# knitRider_T_1_4_redukce_led.net
KiCad netlist of a schematic drawn in EAGLE
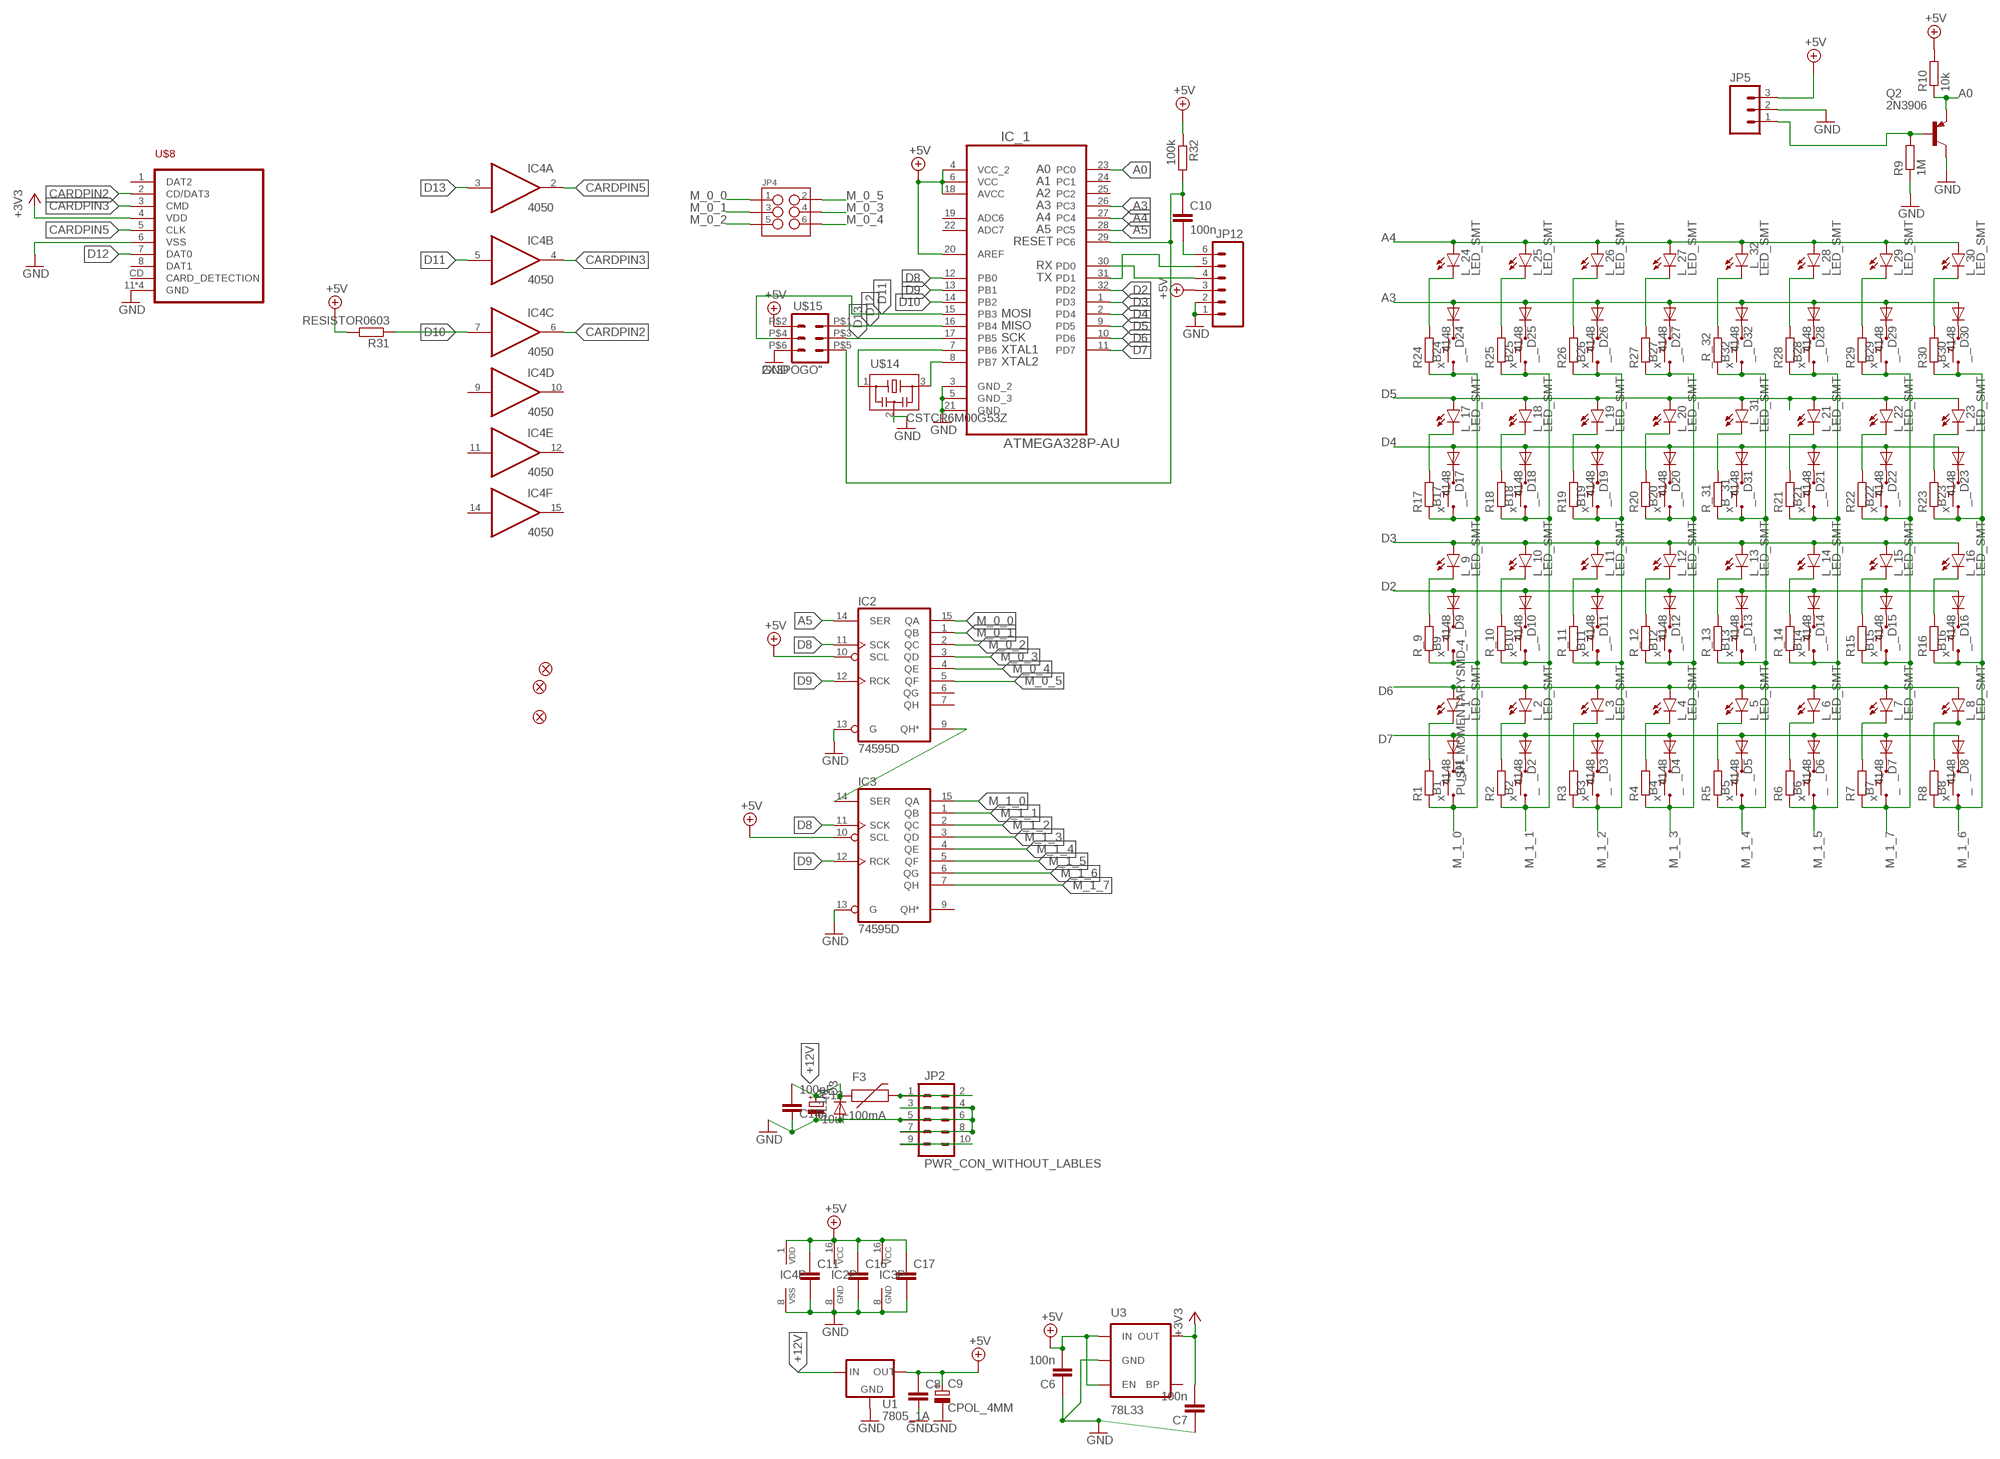
[diagram p0: schematic, sheet 1]

(export (version "E")
  (design (tool "Eeschema 10.0.6"))
  (components
    (comp (ref "B1")
      (value "PUSH_MOMENTARYSMD-4")
      (footprint "eagle-import:TACTILE_SWITCH_TALL")
      (libsource (lib "eagle-import") (part "PUSH_MOMENTARYSMD-4"))
    )
    (comp (ref "B2")
      (value "_")
      (footprint "eagle-import:TACTILE_SWITCH_TALL")
      (libsource (lib "eagle-import") (part "PUSH_MOMENTARYSMD-4"))
    )
    (comp (ref "B3")
      (value "_")
      (footprint "eagle-import:TACTILE_SWITCH_TALL")
      (libsource (lib "eagle-import") (part "PUSH_MOMENTARYSMD-4"))
    )
    (comp (ref "B4")
      (value "_")
      (footprint "eagle-import:TACTILE_SWITCH_TALL")
      (libsource (lib "eagle-import") (part "PUSH_MOMENTARYSMD-4"))
    )
    (comp (ref "B5")
      (value "_")
      (footprint "eagle-import:TACTILE_SWITCH_TALL")
      (libsource (lib "eagle-import") (part "PUSH_MOMENTARYSMD-4"))
    )
    (comp (ref "B6")
      (value "_")
      (footprint "eagle-import:TACTILE_SWITCH_TALL")
      (libsource (lib "eagle-import") (part "PUSH_MOMENTARYSMD-4"))
    )
    (comp (ref "B7")
      (value "_")
      (footprint "eagle-import:TACTILE_SWITCH_TALL")
      (libsource (lib "eagle-import") (part "PUSH_MOMENTARYSMD-4"))
    )
    (comp (ref "B8")
      (value "_")
      (footprint "eagle-import:TACTILE_SWITCH_TALL")
      (libsource (lib "eagle-import") (part "PUSH_MOMENTARYSMD-4"))
    )
    (comp (ref "B9")
      (value "_")
      (footprint "eagle-import:TACTILE_SWITCH_TALL")
      (libsource (lib "eagle-import") (part "PUSH_MOMENTARYSMD-4"))
    )
    (comp (ref "B10")
      (value "_")
      (footprint "eagle-import:TACTILE_SWITCH_TALL")
      (libsource (lib "eagle-import") (part "PUSH_MOMENTARYSMD-4"))
    )
    (comp (ref "B11")
      (value "_")
      (footprint "eagle-import:TACTILE_SWITCH_TALL")
      (libsource (lib "eagle-import") (part "PUSH_MOMENTARYSMD-4"))
    )
    (comp (ref "B12")
      (value "_")
      (footprint "eagle-import:TACTILE_SWITCH_TALL")
      (libsource (lib "eagle-import") (part "PUSH_MOMENTARYSMD-4"))
    )
    (comp (ref "B13")
      (value "_")
      (footprint "eagle-import:TACTILE_SWITCH_TALL")
      (libsource (lib "eagle-import") (part "PUSH_MOMENTARYSMD-4"))
    )
    (comp (ref "B14")
      (value "_")
      (footprint "eagle-import:TACTILE_SWITCH_TALL")
      (libsource (lib "eagle-import") (part "PUSH_MOMENTARYSMD-4"))
    )
    (comp (ref "B15")
      (value "_")
      (footprint "eagle-import:TACTILE_SWITCH_TALL")
      (libsource (lib "eagle-import") (part "PUSH_MOMENTARYSMD-4"))
    )
    (comp (ref "B16")
      (value "_")
      (footprint "eagle-import:TACTILE_SWITCH_TALL")
      (libsource (lib "eagle-import") (part "PUSH_MOMENTARYSMD-4"))
    )
    (comp (ref "B17")
      (value "_")
      (footprint "eagle-import:TACTILE_SWITCH_TALL")
      (libsource (lib "eagle-import") (part "PUSH_MOMENTARYSMD-4"))
    )
    (comp (ref "B18")
      (value "_")
      (footprint "eagle-import:TACTILE_SWITCH_TALL")
      (libsource (lib "eagle-import") (part "PUSH_MOMENTARYSMD-4"))
    )
    (comp (ref "B19")
      (value "_")
      (footprint "eagle-import:TACTILE_SWITCH_TALL")
      (libsource (lib "eagle-import") (part "PUSH_MOMENTARYSMD-4"))
    )
    (comp (ref "B20")
      (value "_")
      (footprint "eagle-import:TACTILE_SWITCH_TALL")
      (libsource (lib "eagle-import") (part "PUSH_MOMENTARYSMD-4"))
    )
    (comp (ref "B21")
      (value "_")
      (footprint "eagle-import:TACTILE_SWITCH_TALL")
      (libsource (lib "eagle-import") (part "PUSH_MOMENTARYSMD-4"))
    )
    (comp (ref "B22")
      (value "_")
      (footprint "eagle-import:TACTILE_SWITCH_TALL")
      (libsource (lib "eagle-import") (part "PUSH_MOMENTARYSMD-4"))
    )
    (comp (ref "B23")
      (value "_")
      (footprint "eagle-import:TACTILE_SWITCH_TALL")
      (libsource (lib "eagle-import") (part "PUSH_MOMENTARYSMD-4"))
    )
    (comp (ref "B24")
      (value "_")
      (footprint "eagle-import:TACTILE_SWITCH_TALL")
      (libsource (lib "eagle-import") (part "PUSH_MOMENTARYSMD-4"))
    )
    (comp (ref "B25")
      (value "_")
      (footprint "eagle-import:TACTILE_SWITCH_TALL")
      (libsource (lib "eagle-import") (part "PUSH_MOMENTARYSMD-4"))
    )
    (comp (ref "B26")
      (value "_")
      (footprint "eagle-import:TACTILE_SWITCH_TALL")
      (libsource (lib "eagle-import") (part "PUSH_MOMENTARYSMD-4"))
    )
    (comp (ref "B27")
      (value "_")
      (footprint "eagle-import:TACTILE_SWITCH_TALL")
      (libsource (lib "eagle-import") (part "PUSH_MOMENTARYSMD-4"))
    )
    (comp (ref "B28")
      (value "_")
      (footprint "eagle-import:TACTILE_SWITCH_TALL")
      (libsource (lib "eagle-import") (part "PUSH_MOMENTARYSMD-4"))
    )
    (comp (ref "B29")
      (value "_")
      (footprint "eagle-import:TACTILE_SWITCH_TALL")
      (libsource (lib "eagle-import") (part "PUSH_MOMENTARYSMD-4"))
    )
    (comp (ref "B30")
      (value "_")
      (footprint "eagle-import:TACTILE_SWITCH_TALL")
      (libsource (lib "eagle-import") (part "PUSH_MOMENTARYSMD-4"))
    )
    (comp (ref "B32")
      (value "_")
      (footprint "eagle-import:TACTILE_SWITCH_TALL")
      (libsource (lib "eagle-import") (part "PUSH_MOMENTARYSMD-4"))
    )
    (comp (ref "B_31")
      (value "_")
      (footprint "eagle-import:TACTILE_SWITCH_TALL")
      (libsource (lib "eagle-import") (part "PUSH_MOMENTARYSMD-4"))
    )
    (comp (ref "C6")
      (value "100n")
      (footprint "eagle-import:CAPACITOR0603")
      (libsource (lib "eagle-import") (part "CAPACITOR0603"))
    )
    (comp (ref "C7")
      (value "100n")
      (footprint "eagle-import:CAPACITOR0603")
      (libsource (lib "eagle-import") (part "CAPACITOR0603"))
    )
    (comp (ref "C8")
      (value "CAPACITOR0603")
      (footprint "eagle-import:CAPACITOR0603")
      (libsource (lib "eagle-import") (part "CAPACITOR0603"))
    )
    (comp (ref "C9")
      (value "CPOL_4MM")
      (footprint "eagle-import:CPOL_4MM")
      (libsource (lib "eagle-import") (part "CPOL_4MM"))
    )
    (comp (ref "C10")
      (value "100n")
      (footprint "eagle-import:CAPACITOR0603")
      (libsource (lib "eagle-import") (part "CAPACITOR0603"))
    )
    (comp (ref "C11")
      (value "CAPACITOR0603")
      (footprint "eagle-import:CAPACITOR0603")
      (libsource (lib "eagle-import") (part "CAPACITOR0603"))
    )
    (comp (ref "C12")
      (value "10uF")
      (footprint "eagle-import:CPOL_4MM")
      (libsource (lib "eagle-import") (part "CPOL_4MM"))
    )
    (comp (ref "C14")
      (value "100nF")
      (footprint "eagle-import:CAPACITOR0603")
      (libsource (lib "eagle-import") (part "CAPACITOR0603"))
    )
    (comp (ref "C16")
      (value "CAPACITOR0603")
      (footprint "eagle-import:CAPACITOR0603")
      (libsource (lib "eagle-import") (part "CAPACITOR0603"))
    )
    (comp (ref "C17")
      (value "CAPACITOR0603")
      (footprint "eagle-import:CAPACITOR0603")
      (libsource (lib "eagle-import") (part "CAPACITOR0603"))
    )
    (comp (ref "D3")
      (value "SL1M")
      (footprint "eagle-import:SOD123")
      (libsource (lib "eagle-import") (part "SL1M"))
    )
    (comp (ref "F3")
      (value "100mA")
      (footprint "eagle-import:PTC0805")
      (libsource (lib "eagle-import") (part "PTC_0805"))
    )
    (comp (ref "FID1")
      (value "FIDUCIAL")
      (footprint "eagle-import:FIDUCIAL")
      (libsource (lib "eagle-import") (part "FIDUCIAL"))
    )
    (comp (ref "FID2")
      (value "FIDUCIAL")
      (footprint "eagle-import:FIDUCIAL")
      (libsource (lib "eagle-import") (part "FIDUCIAL"))
    )
    (comp (ref "FID3")
      (value "FIDUCIAL")
      (footprint "eagle-import:FIDUCIAL")
      (libsource (lib "eagle-import") (part "FIDUCIAL"))
    )
    (comp (ref "IC2")
      (value "74595D")
      (footprint "eagle-import:SO16")
      (fields (field (name "MPN") "SN74HC595DR"))
      (libsource (lib "eagle-import") (part "74595D"))
    )
    (comp (ref "IC3")
      (value "74595D")
      (footprint "eagle-import:SO16")
      (fields (field (name "MPN") "SN74HC595DR"))
      (libsource (lib "eagle-import") (part "74595D"))
    )
    (comp (ref "IC4")
      (value "4050")
      (footprint "eagle-import:SO16")
      (fields (field (name "MPN") "CD4050BDR"))
      (libsource (lib "eagle-import") (part "4050"))
    )
    (comp (ref "IC_1")
      (value "ATMEGA328P-AU")
      (footprint "eagle-import:TQFP32")
      (libsource (lib "eagle-import") (part "ATMEGA328P-AU"))
    )
    (comp (ref "JP2")
      (value "PWR_CON_WITHOUT_LABLES")
      (footprint "eagle-import:PWR_CON_WITHOUT_LABLES")
      (libsource (lib "eagle-import") (part "PWR_CON_WITHOUT_LABLES"))
    )
    (comp (ref "JP4")
      (value "M03X2NO_SILK")
      (footprint "eagle-import:2X3-NS")
      (libsource (lib "eagle-import") (part "M03X2NO_SILK"))
    )
    (comp (ref "JP5")
      (value "M03LOCK")
      (footprint "eagle-import:1X03_LOCK")
      (libsource (lib "eagle-import") (part "M03LOCK"))
    )
    (comp (ref "JP12")
      (value "M06LOCK")
      (footprint "eagle-import:1X06_LOCK")
      (libsource (lib "eagle-import") (part "M06LOCK"))
    )
    (comp (ref "L_1")
      (value "LED_SMT")
      (footprint "eagle-import:LED_0603")
      (libsource (lib "eagle-import") (part "LED_SMT"))
    )
    (comp (ref "L_2")
      (value "LED_SMT")
      (footprint "eagle-import:LED_0603")
      (libsource (lib "eagle-import") (part "LED_SMT"))
    )
    (comp (ref "L_3")
      (value "LED_SMT")
      (footprint "eagle-import:LED_0603")
      (libsource (lib "eagle-import") (part "LED_SMT"))
    )
    (comp (ref "L_4")
      (value "LED_SMT")
      (footprint "eagle-import:LED_0603")
      (libsource (lib "eagle-import") (part "LED_SMT"))
    )
    (comp (ref "L_5")
      (value "LED_SMT")
      (footprint "eagle-import:LED_0603")
      (libsource (lib "eagle-import") (part "LED_SMT"))
    )
    (comp (ref "L_6")
      (value "LED_SMT")
      (footprint "eagle-import:LED_0603")
      (libsource (lib "eagle-import") (part "LED_SMT"))
    )
    (comp (ref "L_7")
      (value "LED_SMT")
      (footprint "eagle-import:LED_0603")
      (libsource (lib "eagle-import") (part "LED_SMT"))
    )
    (comp (ref "L_8")
      (value "LED_SMT")
      (footprint "eagle-import:LED_0603")
      (libsource (lib "eagle-import") (part "LED_SMT"))
    )
    (comp (ref "L_9")
      (value "LED_SMT")
      (footprint "eagle-import:LED_0603")
      (libsource (lib "eagle-import") (part "LED_SMT"))
    )
    (comp (ref "L_10")
      (value "LED_SMT")
      (footprint "eagle-import:LED_0603")
      (libsource (lib "eagle-import") (part "LED_SMT"))
    )
    (comp (ref "L_11")
      (value "LED_SMT")
      (footprint "eagle-import:LED_0603")
      (libsource (lib "eagle-import") (part "LED_SMT"))
    )
    (comp (ref "L_12")
      (value "LED_SMT")
      (footprint "eagle-import:LED_0603")
      (libsource (lib "eagle-import") (part "LED_SMT"))
    )
    (comp (ref "L_13")
      (value "LED_SMT")
      (footprint "eagle-import:LED_0603")
      (libsource (lib "eagle-import") (part "LED_SMT"))
    )
    (comp (ref "L_14")
      (value "LED_SMT")
      (footprint "eagle-import:LED_0603")
      (libsource (lib "eagle-import") (part "LED_SMT"))
    )
    (comp (ref "L_15")
      (value "LED_SMT")
      (footprint "eagle-import:LED_0603")
      (libsource (lib "eagle-import") (part "LED_SMT"))
    )
    (comp (ref "L_16")
      (value "LED_SMT")
      (footprint "eagle-import:LED_0603")
      (libsource (lib "eagle-import") (part "LED_SMT"))
    )
    (comp (ref "L_17")
      (value "LED_SMT")
      (footprint "eagle-import:LED_0603")
      (libsource (lib "eagle-import") (part "LED_SMT"))
    )
    (comp (ref "L_18")
      (value "LED_SMT")
      (footprint "eagle-import:LED_0603")
      (libsource (lib "eagle-import") (part "LED_SMT"))
    )
    (comp (ref "L_19")
      (value "LED_SMT")
      (footprint "eagle-import:LED_0603")
      (libsource (lib "eagle-import") (part "LED_SMT"))
    )
    (comp (ref "L_20")
      (value "LED_SMT")
      (footprint "eagle-import:LED_0603")
      (libsource (lib "eagle-import") (part "LED_SMT"))
    )
    (comp (ref "L_21")
      (value "LED_SMT")
      (footprint "eagle-import:LED_0603")
      (libsource (lib "eagle-import") (part "LED_SMT"))
    )
    (comp (ref "L_22")
      (value "LED_SMT")
      (footprint "eagle-import:LED_0603")
      (libsource (lib "eagle-import") (part "LED_SMT"))
    )
    (comp (ref "L_23")
      (value "LED_SMT")
      (footprint "eagle-import:LED_0603")
      (libsource (lib "eagle-import") (part "LED_SMT"))
    )
    (comp (ref "L_24")
      (value "LED_SMT")
      (footprint "eagle-import:LED_0603")
      (libsource (lib "eagle-import") (part "LED_SMT"))
    )
    (comp (ref "L_25")
      (value "LED_SMT")
      (footprint "eagle-import:LED_0603")
      (libsource (lib "eagle-import") (part "LED_SMT"))
    )
    (comp (ref "L_26")
      (value "LED_SMT")
      (footprint "eagle-import:LED_0603")
      (libsource (lib "eagle-import") (part "LED_SMT"))
    )
    (comp (ref "L_27")
      (value "LED_SMT")
      (footprint "eagle-import:LED_0603")
      (libsource (lib "eagle-import") (part "LED_SMT"))
    )
    (comp (ref "L_28")
      (value "LED_SMT")
      (footprint "eagle-import:LED_0603")
      (libsource (lib "eagle-import") (part "LED_SMT"))
    )
    (comp (ref "L_29")
      (value "LED_SMT")
      (footprint "eagle-import:LED_0603")
      (libsource (lib "eagle-import") (part "LED_SMT"))
    )
    (comp (ref "L_30")
      (value "LED_SMT")
      (footprint "eagle-import:LED_0603")
      (libsource (lib "eagle-import") (part "LED_SMT"))
    )
    (comp (ref "Q2")
      (value "2N3906")
      (footprint "eagle-import:SOT23")
      (fields (field (name "MPN") "MMBT3906LT1G"))
      (libsource (lib "eagle-import") (part "2N3906"))
    )
    (comp (ref "R1")
      (value "x")
      (footprint "eagle-import:RESISTOR0603")
      (libsource (lib "eagle-import") (part "RESISTOR0603"))
    )
    (comp (ref "R2")
      (value "x")
      (footprint "eagle-import:RESISTOR0603")
      (libsource (lib "eagle-import") (part "RESISTOR0603"))
    )
    (comp (ref "R3")
      (value "x")
      (footprint "eagle-import:RESISTOR0603")
      (libsource (lib "eagle-import") (part "RESISTOR0603"))
    )
    (comp (ref "R4")
      (value "x")
      (footprint "eagle-import:RESISTOR0603")
      (libsource (lib "eagle-import") (part "RESISTOR0603"))
    )
    (comp (ref "R5")
      (value "x")
      (footprint "eagle-import:RESISTOR0603")
      (libsource (lib "eagle-import") (part "RESISTOR0603"))
    )
    (comp (ref "R6")
      (value "x")
      (footprint "eagle-import:RESISTOR0603")
      (libsource (lib "eagle-import") (part "RESISTOR0603"))
    )
    (comp (ref "R7")
      (value "x")
      (footprint "eagle-import:RESISTOR0603")
      (libsource (lib "eagle-import") (part "RESISTOR0603"))
    )
    (comp (ref "R8")
      (value "x")
      (footprint "eagle-import:RESISTOR0603")
      (libsource (lib "eagle-import") (part "RESISTOR0603"))
    )
    (comp (ref "R9")
      (value "1M")
      (footprint "eagle-import:RESISTOR0603")
      (libsource (lib "eagle-import") (part "RESISTOR0603"))
    )
    (comp (ref "R10")
      (value "10k")
      (footprint "eagle-import:RESISTOR0603")
      (libsource (lib "eagle-import") (part "RESISTOR0603"))
    )
    (comp (ref "R15")
      (value "x")
      (footprint "eagle-import:RESISTOR0603")
      (libsource (lib "eagle-import") (part "RESISTOR0603"))
    )
    (comp (ref "R16")
      (value "x")
      (footprint "eagle-import:RESISTOR0603")
      (libsource (lib "eagle-import") (part "RESISTOR0603"))
    )
    (comp (ref "R17")
      (value "x")
      (footprint "eagle-import:RESISTOR0603")
      (libsource (lib "eagle-import") (part "RESISTOR0603"))
    )
    (comp (ref "R18")
      (value "x")
      (footprint "eagle-import:RESISTOR0603")
      (libsource (lib "eagle-import") (part "RESISTOR0603"))
    )
    (comp (ref "R19")
      (value "x")
      (footprint "eagle-import:RESISTOR0603")
      (libsource (lib "eagle-import") (part "RESISTOR0603"))
    )
    (comp (ref "R20")
      (value "x")
      (footprint "eagle-import:RESISTOR0603")
      (libsource (lib "eagle-import") (part "RESISTOR0603"))
    )
    (comp (ref "R21")
      (value "x")
      (footprint "eagle-import:RESISTOR0603")
      (libsource (lib "eagle-import") (part "RESISTOR0603"))
    )
    (comp (ref "R22")
      (value "x")
      (footprint "eagle-import:RESISTOR0603")
      (libsource (lib "eagle-import") (part "RESISTOR0603"))
    )
    (comp (ref "R23")
      (value "x")
      (footprint "eagle-import:RESISTOR0603")
      (libsource (lib "eagle-import") (part "RESISTOR0603"))
    )
    (comp (ref "R24")
      (value "x")
      (footprint "eagle-import:RESISTOR0603")
      (libsource (lib "eagle-import") (part "RESISTOR0603"))
    )
    (comp (ref "R25")
      (value "x")
      (footprint "eagle-import:RESISTOR0603")
      (libsource (lib "eagle-import") (part "RESISTOR0603"))
    )
    (comp (ref "R26")
      (value "x")
      (footprint "eagle-import:RESISTOR0603")
      (libsource (lib "eagle-import") (part "RESISTOR0603"))
    )
    (comp (ref "R27")
      (value "x")
      (footprint "eagle-import:RESISTOR0603")
      (libsource (lib "eagle-import") (part "RESISTOR0603"))
    )
    (comp (ref "R28")
      (value "x")
      (footprint "eagle-import:RESISTOR0603")
      (libsource (lib "eagle-import") (part "RESISTOR0603"))
    )
    (comp (ref "R29")
      (value "x")
      (footprint "eagle-import:RESISTOR0603")
      (libsource (lib "eagle-import") (part "RESISTOR0603"))
    )
    (comp (ref "R30")
      (value "x")
      (footprint "eagle-import:RESISTOR0603")
      (libsource (lib "eagle-import") (part "RESISTOR0603"))
    )
    (comp (ref "R31")
      (value "RESISTOR0603")
      (footprint "eagle-import:RESISTOR0603")
      (libsource (lib "eagle-import") (part "RESISTOR0603"))
    )
    (comp (ref "R32")
      (value "100k")
      (footprint "eagle-import:RESISTOR0603")
      (libsource (lib "eagle-import") (part "RESISTOR0603"))
    )
    (comp (ref "R_9")
      (value "x")
      (footprint "eagle-import:RESISTOR0603")
      (libsource (lib "eagle-import") (part "RESISTOR0603"))
    )
    (comp (ref "R_10")
      (value "x")
      (footprint "eagle-import:RESISTOR0603")
      (libsource (lib "eagle-import") (part "RESISTOR0603"))
    )
    (comp (ref "R_11")
      (value "x")
      (footprint "eagle-import:RESISTOR0603")
      (libsource (lib "eagle-import") (part "RESISTOR0603"))
    )
    (comp (ref "R_12")
      (value "x")
      (footprint "eagle-import:RESISTOR0603")
      (libsource (lib "eagle-import") (part "RESISTOR0603"))
    )
    (comp (ref "R_13")
      (value "x")
      (footprint "eagle-import:RESISTOR0603")
      (libsource (lib "eagle-import") (part "RESISTOR0603"))
    )
    (comp (ref "R_14")
      (value "x")
      (footprint "eagle-import:RESISTOR0603")
      (libsource (lib "eagle-import") (part "RESISTOR0603"))
    )
    (comp (ref "R_31")
      (value "x")
      (footprint "eagle-import:RESISTOR0603")
      (libsource (lib "eagle-import") (part "RESISTOR0603"))
    )
    (comp (ref "U$8")
      (value "SD_CARD_SLOT")
      (footprint "eagle-import:MICRO_SD_CARD_SLOT")
      (libsource (lib "eagle-import") (part "SD_CARD_SLOT"))
    )
    (comp (ref "U$14")
      (value "CSTCR6M00G53Z")
      (footprint "eagle-import:CSTCR6M")
      (fields (field (name "MPN") "CSTCR6M00G53-R0"))
      (libsource (lib "eagle-import") (part "CSTCR6M00G53Z"))
    )
    (comp (ref "U$15")
      (value "2X3POGO\"")
      (footprint "eagle-import:2X3_POGO")
      (libsource (lib "eagle-import") (part "2X3POGO{dblquote}"))
    )
    (comp (ref "U1")
      (value "7805_1A")
      (footprint "eagle-import:DPAK")
      (libsource (lib "eagle-import") (part "7805_1A"))
    )
    (comp (ref "U3")
      (value "78L33")
      (footprint "eagle-import:SOT23-5")
      (libsource (lib "eagle-import") (part "V_REG_LDOSMD"))
    )
    (comp (ref "_D1")
      (value "4148")
      (footprint "eagle-import:DIODE_0603")
      (libsource (lib "eagle-import") (part "1N4148_0603"))
    )
    (comp (ref "_D2")
      (value "4148")
      (footprint "eagle-import:DIODE_0603")
      (libsource (lib "eagle-import") (part "1N4148_0603"))
    )
    (comp (ref "_D3")
      (value "4148")
      (footprint "eagle-import:DIODE_0603")
      (libsource (lib "eagle-import") (part "1N4148_0603"))
    )
    (comp (ref "_D4")
      (value "4148")
      (footprint "eagle-import:DIODE_0603")
      (libsource (lib "eagle-import") (part "1N4148_0603"))
    )
    (comp (ref "_D5")
      (value "4148")
      (footprint "eagle-import:DIODE_0603")
      (libsource (lib "eagle-import") (part "1N4148_0603"))
    )
    (comp (ref "_D6")
      (value "4148")
      (footprint "eagle-import:DIODE_0603")
      (libsource (lib "eagle-import") (part "1N4148_0603"))
    )
    (comp (ref "_D7")
      (value "4148")
      (footprint "eagle-import:DIODE_0603")
      (libsource (lib "eagle-import") (part "1N4148_0603"))
    )
    (comp (ref "_D8")
      (value "4148")
      (footprint "eagle-import:DIODE_0603")
      (libsource (lib "eagle-import") (part "1N4148_0603"))
    )
    (comp (ref "_D9")
      (value "4148")
      (footprint "eagle-import:DIODE_0603")
      (libsource (lib "eagle-import") (part "1N4148_0603"))
    )
    (comp (ref "_D10")
      (value "4148")
      (footprint "eagle-import:DIODE_0603")
      (libsource (lib "eagle-import") (part "1N4148_0603"))
    )
    (comp (ref "_D11")
      (value "4148")
      (footprint "eagle-import:DIODE_0603")
      (libsource (lib "eagle-import") (part "1N4148_0603"))
    )
    (comp (ref "_D12")
      (value "4148")
      (footprint "eagle-import:DIODE_0603")
      (libsource (lib "eagle-import") (part "1N4148_0603"))
    )
    (comp (ref "_D13")
      (value "4148")
      (footprint "eagle-import:DIODE_0603")
      (libsource (lib "eagle-import") (part "1N4148_0603"))
    )
    (comp (ref "_D14")
      (value "4148")
      (footprint "eagle-import:DIODE_0603")
      (libsource (lib "eagle-import") (part "1N4148_0603"))
    )
    (comp (ref "_D15")
      (value "4148")
      (footprint "eagle-import:DIODE_0603")
      (libsource (lib "eagle-import") (part "1N4148_0603"))
    )
    (comp (ref "_D16")
      (value "4148")
      (footprint "eagle-import:DIODE_0603")
      (libsource (lib "eagle-import") (part "1N4148_0603"))
    )
    (comp (ref "_D17")
      (value "4148")
      (footprint "eagle-import:DIODE_0603")
      (libsource (lib "eagle-import") (part "1N4148_0603"))
    )
    (comp (ref "_D18")
      (value "4148")
      (footprint "eagle-import:DIODE_0603")
      (libsource (lib "eagle-import") (part "1N4148_0603"))
    )
    (comp (ref "_D19")
      (value "4148")
      (footprint "eagle-import:DIODE_0603")
      (libsource (lib "eagle-import") (part "1N4148_0603"))
    )
    (comp (ref "_D20")
      (value "4148")
      (footprint "eagle-import:DIODE_0603")
      (libsource (lib "eagle-import") (part "1N4148_0603"))
    )
    (comp (ref "_D21")
      (value "4148")
      (footprint "eagle-import:DIODE_0603")
      (libsource (lib "eagle-import") (part "1N4148_0603"))
    )
    (comp (ref "_D22")
      (value "4148")
      (footprint "eagle-import:DIODE_0603")
      (libsource (lib "eagle-import") (part "1N4148_0603"))
    )
    (comp (ref "_D23")
      (value "4148")
      (footprint "eagle-import:DIODE_0603")
      (libsource (lib "eagle-import") (part "1N4148_0603"))
    )
    (comp (ref "_D24")
      (value "4148")
      (footprint "eagle-import:DIODE_0603")
      (libsource (lib "eagle-import") (part "1N4148_0603"))
    )
    (comp (ref "_D25")
      (value "4148")
      (footprint "eagle-import:DIODE_0603")
      (libsource (lib "eagle-import") (part "1N4148_0603"))
    )
    (comp (ref "_D26")
      (value "4148")
      (footprint "eagle-import:DIODE_0603")
      (libsource (lib "eagle-import") (part "1N4148_0603"))
    )
    (comp (ref "_D27")
      (value "4148")
      (footprint "eagle-import:DIODE_0603")
      (libsource (lib "eagle-import") (part "1N4148_0603"))
    )
    (comp (ref "_D28")
      (value "4148")
      (footprint "eagle-import:DIODE_0603")
      (libsource (lib "eagle-import") (part "1N4148_0603"))
    )
    (comp (ref "_D29")
      (value "4148")
      (footprint "eagle-import:DIODE_0603")
      (libsource (lib "eagle-import") (part "1N4148_0603"))
    )
    (comp (ref "_D30")
      (value "4148")
      (footprint "eagle-import:DIODE_0603")
      (libsource (lib "eagle-import") (part "1N4148_0603"))
    )
    (comp (ref "_D31")
      (value "4148")
      (footprint "eagle-import:DIODE_0603")
      (libsource (lib "eagle-import") (part "1N4148_0603"))
    )
    (comp (ref "_D32")
      (value "4148")
      (footprint "eagle-import:DIODE_0603")
      (libsource (lib "eagle-import") (part "1N4148_0603"))
    )
    (comp (ref "_L_31")
      (value "LED_SMT")
      (footprint "eagle-import:LED_0603")
      (libsource (lib "eagle-import") (part "LED_SMT"))
    )
    (comp (ref "_L_32")
      (value "LED_SMT")
      (footprint "eagle-import:LED_0603")
      (libsource (lib "eagle-import") (part "LED_SMT"))
    )
    (comp (ref "_R_32")
      (value "x")
      (footprint "eagle-import:RESISTOR0603")
      (libsource (lib "eagle-import") (part "RESISTOR0603"))
    )
  )
  (nets
    (net (code "1") (name "+3V3") (class "Default")
      (node (ref "C7") (pin "2") (pinfunction "2_2") (pintype "passive"))
      (node (ref "U$8") (pin "4") (pinfunction "VDD_4") (pintype "bidirectional"))
      (node (ref "U3") (pin "5") (pinfunction "OUT_5") (pintype "passive"))
    )
    (net (code "2") (name "+5V") (class "Default")
      (node (ref "C11") (pin "1") (pinfunction "1_1") (pintype "passive"))
      (node (ref "C16") (pin "1") (pinfunction "1_1") (pintype "passive"))
      (node (ref "C17") (pin "1") (pinfunction "1_1") (pintype "passive"))
      (node (ref "C6") (pin "2") (pinfunction "2_2") (pintype "passive"))
      (node (ref "C8") (pin "1") (pinfunction "1_1") (pintype "passive"))
      (node (ref "C9") (pin "+") (pinfunction "+_+") (pintype "passive"))
      (node (ref "IC2") (pin "10") (pinfunction "SCL_10") (pintype "input"))
      (node (ref "IC2") (pin "16") (pinfunction "VCC_16") (pintype "power_in"))
      (node (ref "IC3") (pin "10") (pinfunction "SCL_10") (pintype "input"))
      (node (ref "IC3") (pin "16") (pinfunction "VCC_16") (pintype "power_in"))
      (node (ref "IC4") (pin "1") (pinfunction "VDD_1") (pintype "power_in"))
      (node (ref "IC_1") (pin "18") (pinfunction "AVCC_18") (pintype "power_in"))
      (node (ref "IC_1") (pin "20") (pinfunction "AREF_20") (pintype "input"))
      (node (ref "IC_1") (pin "4") (pinfunction "VCC_2_4") (pintype "power_in"))
      (node (ref "IC_1") (pin "6") (pinfunction "VCC_6") (pintype "power_in"))
      (node (ref "JP12") (pin "3") (pinfunction "3_3") (pintype "passive"))
      (node (ref "JP5") (pin "3") (pinfunction "3_3") (pintype "passive"))
      (node (ref "R10") (pin "2") (pinfunction "2_2") (pintype "passive"))
      (node (ref "R31") (pin "2") (pinfunction "2_2") (pintype "passive"))
      (node (ref "R32") (pin "1") (pinfunction "1_1") (pintype "passive"))
      (node (ref "U$15") (pin "P$2") (pinfunction "2_P$2") (pintype "passive"))
      (node (ref "U1") (pin "3") (pinfunction "OUT_3") (pintype "output"))
      (node (ref "U3") (pin "1") (pinfunction "IN_1") (pintype "input"))
      (node (ref "U3") (pin "3") (pinfunction "EN_3") (pintype "input"))
    )
    (net (code "3") (name "+12V") (class "Default")
      (node (ref "C12") (pin "+") (pinfunction "+_+") (pintype "passive"))
      (node (ref "C14") (pin "2") (pinfunction "2_2") (pintype "passive"))
      (node (ref "D3") (pin "C") (pinfunction "C_C") (pintype "passive"))
      (node (ref "F3") (pin "2") (pinfunction "1_2") (pintype "bidirectional"))
      (node (ref "U1") (pin "1") (pinfunction "IN_1") (pintype "input"))
    )
    (net (code "4") (name "A0") (class "Default")
      (node (ref "IC_1") (pin "23") (pinfunction "PC0_23") (pintype "bidirectional"))
      (node (ref "Q2") (pin "E") (pinfunction "E_E") (pintype "passive"))
      (node (ref "R10") (pin "1") (pinfunction "1_1") (pintype "passive"))
    )
    (net (code "5") (name "A3") (class "Default")
      (node (ref "IC_1") (pin "26") (pinfunction "PC3_26") (pintype "bidirectional"))
      (node (ref "_D24") (pin "A") (pinfunction "A_A") (pintype "passive"))
      (node (ref "_D25") (pin "A") (pinfunction "A_A") (pintype "passive"))
      (node (ref "_D26") (pin "A") (pinfunction "A_A") (pintype "passive"))
      (node (ref "_D27") (pin "A") (pinfunction "A_A") (pintype "passive"))
      (node (ref "_D28") (pin "A") (pinfunction "A_A") (pintype "passive"))
      (node (ref "_D29") (pin "A") (pinfunction "A_A") (pintype "passive"))
      (node (ref "_D30") (pin "A") (pinfunction "A_A") (pintype "passive"))
      (node (ref "_D32") (pin "A") (pinfunction "A_A") (pintype "passive"))
    )
    (net (code "6") (name "A4") (class "Default")
      (node (ref "IC_1") (pin "27") (pinfunction "PC4_27") (pintype "bidirectional"))
      (node (ref "L_24") (pin "A") (pinfunction "A_A") (pintype "passive"))
      (node (ref "L_25") (pin "A") (pinfunction "A_A") (pintype "passive"))
      (node (ref "L_26") (pin "A") (pinfunction "A_A") (pintype "passive"))
      (node (ref "L_27") (pin "A") (pinfunction "A_A") (pintype "passive"))
      (node (ref "L_28") (pin "A") (pinfunction "A_A") (pintype "passive"))
      (node (ref "L_29") (pin "A") (pinfunction "A_A") (pintype "passive"))
      (node (ref "L_30") (pin "A") (pinfunction "A_A") (pintype "passive"))
      (node (ref "_L_32") (pin "A") (pinfunction "A_A") (pintype "passive"))
    )
    (net (code "7") (name "A5") (class "Default")
      (node (ref "IC2") (pin "14") (pinfunction "SER_14") (pintype "input"))
      (node (ref "IC_1") (pin "28") (pinfunction "PC5_28") (pintype "bidirectional"))
    )
    (net (code "8") (name "CARDPIN2") (class "Default")
      (node (ref "IC4") (pin "6") (pinfunction "O_6") (pintype "output"))
      (node (ref "U$8") (pin "2") (pinfunction "CD/DAT3_2") (pintype "bidirectional"))
    )
    (net (code "9") (name "CARDPIN3") (class "Default")
      (node (ref "IC4") (pin "4") (pinfunction "O_4") (pintype "output"))
      (node (ref "U$8") (pin "3") (pinfunction "CMD_3") (pintype "bidirectional"))
    )
    (net (code "10") (name "CARDPIN5") (class "Default")
      (node (ref "IC4") (pin "2") (pinfunction "O_2") (pintype "output"))
      (node (ref "U$8") (pin "5") (pinfunction "CLK_5") (pintype "bidirectional"))
    )
    (net (code "11") (name "D2") (class "Default")
      (node (ref "IC_1") (pin "32") (pinfunction "PD2_32") (pintype "bidirectional"))
      (node (ref "_D10") (pin "A") (pinfunction "A_A") (pintype "passive"))
      (node (ref "_D11") (pin "A") (pinfunction "A_A") (pintype "passive"))
      (node (ref "_D12") (pin "A") (pinfunction "A_A") (pintype "passive"))
      (node (ref "_D13") (pin "A") (pinfunction "A_A") (pintype "passive"))
      (node (ref "_D14") (pin "A") (pinfunction "A_A") (pintype "passive"))
      (node (ref "_D15") (pin "A") (pinfunction "A_A") (pintype "passive"))
      (node (ref "_D16") (pin "A") (pinfunction "A_A") (pintype "passive"))
      (node (ref "_D9") (pin "A") (pinfunction "A_A") (pintype "passive"))
    )
    (net (code "12") (name "D3") (class "Default")
      (node (ref "IC_1") (pin "1") (pinfunction "PD3_1") (pintype "bidirectional"))
      (node (ref "L_10") (pin "A") (pinfunction "A_A") (pintype "passive"))
      (node (ref "L_11") (pin "A") (pinfunction "A_A") (pintype "passive"))
      (node (ref "L_12") (pin "A") (pinfunction "A_A") (pintype "passive"))
      (node (ref "L_13") (pin "A") (pinfunction "A_A") (pintype "passive"))
      (node (ref "L_14") (pin "A") (pinfunction "A_A") (pintype "passive"))
      (node (ref "L_15") (pin "A") (pinfunction "A_A") (pintype "passive"))
      (node (ref "L_16") (pin "A") (pinfunction "A_A") (pintype "passive"))
      (node (ref "L_9") (pin "A") (pinfunction "A_A") (pintype "passive"))
    )
    (net (code "13") (name "D4") (class "Default")
      (node (ref "IC_1") (pin "2") (pinfunction "PD4_2") (pintype "bidirectional"))
      (node (ref "_D17") (pin "A") (pinfunction "A_A") (pintype "passive"))
      (node (ref "_D18") (pin "A") (pinfunction "A_A") (pintype "passive"))
      (node (ref "_D19") (pin "A") (pinfunction "A_A") (pintype "passive"))
      (node (ref "_D20") (pin "A") (pinfunction "A_A") (pintype "passive"))
      (node (ref "_D21") (pin "A") (pinfunction "A_A") (pintype "passive"))
      (node (ref "_D22") (pin "A") (pinfunction "A_A") (pintype "passive"))
      (node (ref "_D23") (pin "A") (pinfunction "A_A") (pintype "passive"))
      (node (ref "_D31") (pin "A") (pinfunction "A_A") (pintype "passive"))
    )
    (net (code "14") (name "D5") (class "Default")
      (node (ref "IC_1") (pin "9") (pinfunction "PD5_9") (pintype "bidirectional"))
      (node (ref "L_17") (pin "A") (pinfunction "A_A") (pintype "passive"))
      (node (ref "L_18") (pin "A") (pinfunction "A_A") (pintype "passive"))
      (node (ref "L_19") (pin "A") (pinfunction "A_A") (pintype "passive"))
      (node (ref "L_20") (pin "A") (pinfunction "A_A") (pintype "passive"))
      (node (ref "L_21") (pin "A") (pinfunction "A_A") (pintype "passive"))
      (node (ref "L_22") (pin "A") (pinfunction "A_A") (pintype "passive"))
      (node (ref "L_23") (pin "A") (pinfunction "A_A") (pintype "passive"))
      (node (ref "_L_31") (pin "A") (pinfunction "A_A") (pintype "passive"))
    )
    (net (code "15") (name "D6") (class "Default")
      (node (ref "IC_1") (pin "10") (pinfunction "PD6_10") (pintype "bidirectional"))
      (node (ref "L_1") (pin "A") (pinfunction "A_A") (pintype "passive"))
      (node (ref "L_2") (pin "A") (pinfunction "A_A") (pintype "passive"))
      (node (ref "L_3") (pin "A") (pinfunction "A_A") (pintype "passive"))
      (node (ref "L_4") (pin "A") (pinfunction "A_A") (pintype "passive"))
      (node (ref "L_5") (pin "A") (pinfunction "A_A") (pintype "passive"))
      (node (ref "L_6") (pin "A") (pinfunction "A_A") (pintype "passive"))
      (node (ref "L_7") (pin "A") (pinfunction "A_A") (pintype "passive"))
      (node (ref "L_8") (pin "A") (pinfunction "A_A") (pintype "passive"))
    )
    (net (code "16") (name "D7") (class "Default")
      (node (ref "IC_1") (pin "11") (pinfunction "PD7_11") (pintype "bidirectional"))
      (node (ref "_D1") (pin "A") (pinfunction "A_A") (pintype "passive"))
      (node (ref "_D2") (pin "A") (pinfunction "A_A") (pintype "passive"))
      (node (ref "_D3") (pin "A") (pinfunction "A_A") (pintype "passive"))
      (node (ref "_D4") (pin "A") (pinfunction "A_A") (pintype "passive"))
      (node (ref "_D5") (pin "A") (pinfunction "A_A") (pintype "passive"))
      (node (ref "_D6") (pin "A") (pinfunction "A_A") (pintype "passive"))
      (node (ref "_D7") (pin "A") (pinfunction "A_A") (pintype "passive"))
      (node (ref "_D8") (pin "A") (pinfunction "A_A") (pintype "passive"))
    )
    (net (code "17") (name "D8") (class "Default")
      (node (ref "IC2") (pin "11") (pinfunction "SCK_11") (pintype "input"))
      (node (ref "IC3") (pin "11") (pinfunction "SCK_11") (pintype "input"))
      (node (ref "IC_1") (pin "12") (pinfunction "PB0_12") (pintype "bidirectional"))
    )
    (net (code "18") (name "D9") (class "Default")
      (node (ref "IC2") (pin "12") (pinfunction "RCK_12") (pintype "input"))
      (node (ref "IC3") (pin "12") (pinfunction "RCK_12") (pintype "input"))
      (node (ref "IC_1") (pin "13") (pinfunction "PB1_13") (pintype "bidirectional"))
    )
    (net (code "19") (name "D10") (class "Default")
      (node (ref "IC4") (pin "7") (pinfunction "I_7") (pintype "input"))
      (node (ref "IC_1") (pin "14") (pinfunction "PB2_14") (pintype "bidirectional"))
      (node (ref "R31") (pin "1") (pinfunction "1_1") (pintype "passive"))
    )
    (net (code "20") (name "D11") (class "Default")
      (node (ref "IC4") (pin "5") (pinfunction "I_5") (pintype "input"))
      (node (ref "IC_1") (pin "15") (pinfunction "PB3_15") (pintype "bidirectional"))
      (node (ref "U$15") (pin "P$4") (pinfunction "4_P$4") (pintype "passive"))
    )
    (net (code "21") (name "D12") (class "Default")
      (node (ref "IC_1") (pin "16") (pinfunction "PB4_16") (pintype "bidirectional"))
      (node (ref "U$15") (pin "P$1") (pinfunction "1_P$1") (pintype "passive"))
      (node (ref "U$8") (pin "7") (pinfunction "DAT0_7") (pintype "bidirectional"))
    )
    (net (code "22") (name "D13") (class "Default")
      (node (ref "IC4") (pin "3") (pinfunction "I_3") (pintype "input"))
      (node (ref "IC_1") (pin "17") (pinfunction "PB5_17") (pintype "bidirectional"))
      (node (ref "U$15") (pin "P$3") (pinfunction "3_P$3") (pintype "passive"))
    )
    (net (code "23") (name "GND") (class "Default")
      (node (ref "C11") (pin "2") (pinfunction "2_2") (pintype "passive"))
      (node (ref "C12") (pin "-") (pinfunction "-_-") (pintype "passive"))
      (node (ref "C14") (pin "1") (pinfunction "1_1") (pintype "passive"))
      (node (ref "C16") (pin "2") (pinfunction "2_2") (pintype "passive"))
      (node (ref "C17") (pin "2") (pinfunction "2_2") (pintype "passive"))
      (node (ref "C6") (pin "1") (pinfunction "1_1") (pintype "passive"))
      (node (ref "C7") (pin "1") (pinfunction "1_1") (pintype "passive"))
      (node (ref "C8") (pin "2") (pinfunction "2_2") (pintype "passive"))
      (node (ref "C9") (pin "-") (pinfunction "-_-") (pintype "passive"))
      (node (ref "D3") (pin "A") (pinfunction "A_A") (pintype "passive"))
      (node (ref "IC2") (pin "13") (pinfunction "G_13") (pintype "input"))
      (node (ref "IC2") (pin "8") (pinfunction "GND_8") (pintype "power_in"))
      (node (ref "IC3") (pin "13") (pinfunction "G_13") (pintype "input"))
      (node (ref "IC3") (pin "8") (pinfunction "GND_8") (pintype "power_in"))
      (node (ref "IC4") (pin "8") (pinfunction "VSS_8") (pintype "power_in"))
      (node (ref "IC_1") (pin "21") (pinfunction "GND_21") (pintype "passive"))
      (node (ref "IC_1") (pin "3") (pinfunction "GND_2_3") (pintype "passive"))
      (node (ref "IC_1") (pin "5") (pinfunction "GND_3_5") (pintype "passive"))
      (node (ref "JP12") (pin "1") (pinfunction "1_1") (pintype "passive"))
      (node (ref "JP12") (pin "2") (pinfunction "2_2") (pintype "passive"))
      (node (ref "JP2") (pin "3") (pinfunction "3_3") (pintype "passive"))
      (node (ref "JP2") (pin "4") (pinfunction "4_4") (pintype "passive"))
      (node (ref "JP2") (pin "5") (pinfunction "5_5") (pintype "passive"))
      (node (ref "JP2") (pin "6") (pinfunction "6_6") (pintype "passive"))
      (node (ref "JP2") (pin "7") (pinfunction "7_7") (pintype "passive"))
      (node (ref "JP2") (pin "8") (pinfunction "8_8") (pintype "passive"))
      (node (ref "JP5") (pin "2") (pinfunction "2_2") (pintype "passive"))
      (node (ref "Q2") (pin "C") (pinfunction "C_C") (pintype "passive"))
      (node (ref "R9") (pin "1") (pinfunction "1_1") (pintype "passive"))
      (node (ref "U$14") (pin "2") (pinfunction "2_2") (pintype "passive"))
      (node (ref "U$15") (pin "P$6") (pinfunction "6_P$6") (pintype "passive"))
      (node (ref "U$8") (pin "11") (pinfunction "GND_11") (pintype "bidirectional"))
      (node (ref "U$8") (pin "12") (pinfunction "GND_12") (pintype "bidirectional"))
      (node (ref "U$8") (pin "13") (pinfunction "GND_13") (pintype "bidirectional"))
      (node (ref "U$8") (pin "6") (pinfunction "VSS_6") (pintype "bidirectional"))
      (node (ref "U$8") (pin "G") (pinfunction "GND_G") (pintype "bidirectional"))
      (node (ref "U1") (pin "4") (pinfunction "GND_4") (pintype "input"))
      (node (ref "U3") (pin "2") (pinfunction "GND_2") (pintype "input"))
    )
    (net (code "24") (name "M_0_0") (class "Default")
      (node (ref "IC2") (pin "15") (pinfunction "QA_15") (pintype "tri_state"))
      (node (ref "JP4") (pin "1") (pinfunction "1_1") (pintype "bidirectional"))
    )
    (net (code "25") (name "M_0_1") (class "Default")
      (node (ref "IC2") (pin "1") (pinfunction "QB_1") (pintype "tri_state"))
      (node (ref "JP4") (pin "3") (pinfunction "3_3") (pintype "bidirectional"))
    )
    (net (code "26") (name "M_0_2") (class "Default")
      (node (ref "IC2") (pin "2") (pinfunction "QC_2") (pintype "tri_state"))
      (node (ref "JP4") (pin "5") (pinfunction "5_5") (pintype "bidirectional"))
    )
    (net (code "27") (name "M_0_3") (class "Default")
      (node (ref "IC2") (pin "3") (pinfunction "QD_3") (pintype "tri_state"))
      (node (ref "JP4") (pin "4") (pinfunction "4_4") (pintype "bidirectional"))
    )
    (net (code "28") (name "M_0_4") (class "Default")
      (node (ref "IC2") (pin "4") (pinfunction "QE_4") (pintype "tri_state"))
      (node (ref "JP4") (pin "6") (pinfunction "6_6") (pintype "bidirectional"))
    )
    (net (code "29") (name "M_0_5") (class "Default")
      (node (ref "IC2") (pin "5") (pinfunction "QF_5") (pintype "tri_state"))
      (node (ref "JP4") (pin "2") (pinfunction "2_2") (pintype "bidirectional"))
    )
    (net (code "30") (name "M_1_0") (class "Default")
      (node (ref "B1") (pin "A1") (pinfunction "1_A1") (pintype "passive"))
      (node (ref "B1") (pin "A2") (pinfunction "1_A2") (pintype "passive"))
      (node (ref "B17") (pin "A1") (pinfunction "1_A1") (pintype "passive"))
      (node (ref "B17") (pin "A2") (pinfunction "1_A2") (pintype "passive"))
      (node (ref "B24") (pin "A1") (pinfunction "1_A1") (pintype "passive"))
      (node (ref "B24") (pin "A2") (pinfunction "1_A2") (pintype "passive"))
      (node (ref "B9") (pin "A1") (pinfunction "1_A1") (pintype "passive"))
      (node (ref "B9") (pin "A2") (pinfunction "1_A2") (pintype "passive"))
      (node (ref "IC3") (pin "15") (pinfunction "QA_15") (pintype "tri_state"))
      (node (ref "R1") (pin "1") (pinfunction "1_1") (pintype "passive"))
      (node (ref "R17") (pin "1") (pinfunction "1_1") (pintype "passive"))
      (node (ref "R24") (pin "1") (pinfunction "1_1") (pintype "passive"))
      (node (ref "R_9") (pin "1") (pinfunction "1_1") (pintype "passive"))
    )
    (net (code "31") (name "M_1_1") (class "Default")
      (node (ref "B10") (pin "A1") (pinfunction "1_A1") (pintype "passive"))
      (node (ref "B10") (pin "A2") (pinfunction "1_A2") (pintype "passive"))
      (node (ref "B18") (pin "A1") (pinfunction "1_A1") (pintype "passive"))
      (node (ref "B18") (pin "A2") (pinfunction "1_A2") (pintype "passive"))
      (node (ref "B2") (pin "A1") (pinfunction "1_A1") (pintype "passive"))
      (node (ref "B2") (pin "A2") (pinfunction "1_A2") (pintype "passive"))
      (node (ref "B25") (pin "A1") (pinfunction "1_A1") (pintype "passive"))
      (node (ref "B25") (pin "A2") (pinfunction "1_A2") (pintype "passive"))
      (node (ref "IC3") (pin "1") (pinfunction "QB_1") (pintype "tri_state"))
      (node (ref "R18") (pin "1") (pinfunction "1_1") (pintype "passive"))
      (node (ref "R2") (pin "1") (pinfunction "1_1") (pintype "passive"))
      (node (ref "R25") (pin "1") (pinfunction "1_1") (pintype "passive"))
      (node (ref "R_10") (pin "1") (pinfunction "1_1") (pintype "passive"))
    )
    (net (code "32") (name "M_1_2") (class "Default")
      (node (ref "B11") (pin "A1") (pinfunction "1_A1") (pintype "passive"))
      (node (ref "B11") (pin "A2") (pinfunction "1_A2") (pintype "passive"))
      (node (ref "B19") (pin "A1") (pinfunction "1_A1") (pintype "passive"))
      (node (ref "B19") (pin "A2") (pinfunction "1_A2") (pintype "passive"))
      (node (ref "B26") (pin "A1") (pinfunction "1_A1") (pintype "passive"))
      (node (ref "B26") (pin "A2") (pinfunction "1_A2") (pintype "passive"))
      (node (ref "B3") (pin "A1") (pinfunction "1_A1") (pintype "passive"))
      (node (ref "B3") (pin "A2") (pinfunction "1_A2") (pintype "passive"))
      (node (ref "IC3") (pin "2") (pinfunction "QC_2") (pintype "tri_state"))
      (node (ref "R19") (pin "1") (pinfunction "1_1") (pintype "passive"))
      (node (ref "R26") (pin "1") (pinfunction "1_1") (pintype "passive"))
      (node (ref "R3") (pin "1") (pinfunction "1_1") (pintype "passive"))
      (node (ref "R_11") (pin "1") (pinfunction "1_1") (pintype "passive"))
    )
    (net (code "33") (name "M_1_3") (class "Default")
      (node (ref "B12") (pin "A1") (pinfunction "1_A1") (pintype "passive"))
      (node (ref "B12") (pin "A2") (pinfunction "1_A2") (pintype "passive"))
      (node (ref "B20") (pin "A1") (pinfunction "1_A1") (pintype "passive"))
      (node (ref "B20") (pin "A2") (pinfunction "1_A2") (pintype "passive"))
      (node (ref "B27") (pin "A1") (pinfunction "1_A1") (pintype "passive"))
      (node (ref "B27") (pin "A2") (pinfunction "1_A2") (pintype "passive"))
      (node (ref "B4") (pin "A1") (pinfunction "1_A1") (pintype "passive"))
      (node (ref "B4") (pin "A2") (pinfunction "1_A2") (pintype "passive"))
      (node (ref "IC3") (pin "3") (pinfunction "QD_3") (pintype "tri_state"))
      (node (ref "R20") (pin "1") (pinfunction "1_1") (pintype "passive"))
      (node (ref "R27") (pin "1") (pinfunction "1_1") (pintype "passive"))
      (node (ref "R4") (pin "1") (pinfunction "1_1") (pintype "passive"))
      (node (ref "R_12") (pin "1") (pinfunction "1_1") (pintype "passive"))
    )
    (net (code "34") (name "M_1_4") (class "Default")
      (node (ref "B13") (pin "A1") (pinfunction "1_A1") (pintype "passive"))
      (node (ref "B13") (pin "A2") (pinfunction "1_A2") (pintype "passive"))
      (node (ref "B32") (pin "A1") (pinfunction "1_A1") (pintype "passive"))
      (node (ref "B32") (pin "A2") (pinfunction "1_A2") (pintype "passive"))
      (node (ref "B5") (pin "A1") (pinfunction "1_A1") (pintype "passive"))
      (node (ref "B5") (pin "A2") (pinfunction "1_A2") (pintype "passive"))
      (node (ref "B_31") (pin "A1") (pinfunction "1_A1") (pintype "passive"))
      (node (ref "B_31") (pin "A2") (pinfunction "1_A2") (pintype "passive"))
      (node (ref "IC3") (pin "4") (pinfunction "QE_4") (pintype "tri_state"))
      (node (ref "R5") (pin "1") (pinfunction "1_1") (pintype "passive"))
      (node (ref "R_13") (pin "1") (pinfunction "1_1") (pintype "passive"))
      (node (ref "R_31") (pin "1") (pinfunction "1_1") (pintype "passive"))
      (node (ref "_R_32") (pin "1") (pinfunction "1_1") (pintype "passive"))
    )
    (net (code "35") (name "M_1_5") (class "Default")
      (node (ref "B14") (pin "A1") (pinfunction "1_A1") (pintype "passive"))
      (node (ref "B14") (pin "A2") (pinfunction "1_A2") (pintype "passive"))
      (node (ref "B21") (pin "A1") (pinfunction "1_A1") (pintype "passive"))
      (node (ref "B21") (pin "A2") (pinfunction "1_A2") (pintype "passive"))
      (node (ref "B28") (pin "A1") (pinfunction "1_A1") (pintype "passive"))
      (node (ref "B28") (pin "A2") (pinfunction "1_A2") (pintype "passive"))
      (node (ref "B6") (pin "A1") (pinfunction "1_A1") (pintype "passive"))
      (node (ref "B6") (pin "A2") (pinfunction "1_A2") (pintype "passive"))
      (node (ref "IC3") (pin "5") (pinfunction "QF_5") (pintype "tri_state"))
      (node (ref "R21") (pin "1") (pinfunction "1_1") (pintype "passive"))
      (node (ref "R28") (pin "1") (pinfunction "1_1") (pintype "passive"))
      (node (ref "R6") (pin "1") (pinfunction "1_1") (pintype "passive"))
      (node (ref "R_14") (pin "1") (pinfunction "1_1") (pintype "passive"))
    )
    (net (code "36") (name "M_1_6") (class "Default")
      (node (ref "B16") (pin "A1") (pinfunction "1_A1") (pintype "passive"))
      (node (ref "B16") (pin "A2") (pinfunction "1_A2") (pintype "passive"))
      (node (ref "B23") (pin "A1") (pinfunction "1_A1") (pintype "passive"))
      (node (ref "B23") (pin "A2") (pinfunction "1_A2") (pintype "passive"))
      (node (ref "B30") (pin "A1") (pinfunction "1_A1") (pintype "passive"))
      (node (ref "B30") (pin "A2") (pinfunction "1_A2") (pintype "passive"))
      (node (ref "B8") (pin "A1") (pinfunction "1_A1") (pintype "passive"))
      (node (ref "B8") (pin "A2") (pinfunction "1_A2") (pintype "passive"))
      (node (ref "IC3") (pin "6") (pinfunction "QG_6") (pintype "tri_state"))
      (node (ref "R16") (pin "1") (pinfunction "1_1") (pintype "passive"))
      (node (ref "R23") (pin "1") (pinfunction "1_1") (pintype "passive"))
      (node (ref "R30") (pin "1") (pinfunction "1_1") (pintype "passive"))
      (node (ref "R8") (pin "1") (pinfunction "1_1") (pintype "passive"))
    )
    (net (code "37") (name "M_1_7") (class "Default")
      (node (ref "B15") (pin "A1") (pinfunction "1_A1") (pintype "passive"))
      (node (ref "B15") (pin "A2") (pinfunction "1_A2") (pintype "passive"))
      (node (ref "B22") (pin "A1") (pinfunction "1_A1") (pintype "passive"))
      (node (ref "B22") (pin "A2") (pinfunction "1_A2") (pintype "passive"))
      (node (ref "B29") (pin "A1") (pinfunction "1_A1") (pintype "passive"))
      (node (ref "B29") (pin "A2") (pinfunction "1_A2") (pintype "passive"))
      (node (ref "B7") (pin "A1") (pinfunction "1_A1") (pintype "passive"))
      (node (ref "B7") (pin "A2") (pinfunction "1_A2") (pintype "passive"))
      (node (ref "IC3") (pin "7") (pinfunction "QH_7") (pintype "tri_state"))
      (node (ref "R15") (pin "1") (pinfunction "1_1") (pintype "passive"))
      (node (ref "R22") (pin "1") (pinfunction "1_1") (pintype "passive"))
      (node (ref "R29") (pin "1") (pinfunction "1_1") (pintype "passive"))
      (node (ref "R7") (pin "1") (pinfunction "1_1") (pintype "passive"))
    )
    (net (code "38") (name "Net-(C10-Pad2)") (class "Default")
      (node (ref "C10") (pin "2") (pinfunction "2_2") (pintype "passive"))
      (node (ref "JP12") (pin "6") (pinfunction "6_6") (pintype "passive"))
    )
    (net (code "39") (name "Net-(F3-2)") (class "Default")
      (node (ref "F3") (pin "3") (pinfunction "2_3") (pintype "bidirectional"))
      (node (ref "JP2") (pin "1") (pinfunction "1_1") (pintype "passive"))
      (node (ref "JP2") (pin "2") (pinfunction "2_2") (pintype "passive"))
    )
    (net (code "40") (name "Net-(IC2A-QH*)") (class "Default")
      (node (ref "IC2") (pin "9") (pinfunction "QH*_9") (pintype "tri_state"))
      (node (ref "IC3") (pin "14") (pinfunction "SER_14") (pintype "input"))
    )
    (net (code "41") (name "Net-(IC_1-PB6)") (class "Default")
      (node (ref "IC_1") (pin "7") (pinfunction "PB6_7") (pintype "bidirectional"))
      (node (ref "U$14") (pin "1") (pinfunction "1_1") (pintype "passive"))
    )
    (net (code "42") (name "Net-(IC_1-PB7)") (class "Default")
      (node (ref "IC_1") (pin "8") (pinfunction "PB7_8") (pintype "bidirectional"))
      (node (ref "U$14") (pin "3") (pinfunction "3_3") (pintype "passive"))
    )
    (net (code "43") (name "Net-(IC_1-PC6)") (class "Default")
      (node (ref "C10") (pin "1") (pinfunction "1_1") (pintype "passive"))
      (node (ref "IC_1") (pin "29") (pinfunction "PC6_29") (pintype "bidirectional"))
      (node (ref "R32") (pin "2") (pinfunction "2_2") (pintype "passive"))
      (node (ref "U$15") (pin "P$5") (pinfunction "5_P$5") (pintype "passive"))
    )
    (net (code "44") (name "Net-(IC_1-PD0)") (class "Default")
      (node (ref "IC_1") (pin "30") (pinfunction "PD0_30") (pintype "bidirectional"))
      (node (ref "JP12") (pin "4") (pinfunction "4_4") (pintype "passive"))
    )
    (net (code "45") (name "Net-(IC_1-PD1)") (class "Default")
      (node (ref "IC_1") (pin "31") (pinfunction "PD1_31") (pintype "bidirectional"))
      (node (ref "JP12") (pin "5") (pinfunction "5_5") (pintype "passive"))
    )
    (net (code "46") (name "Net-(JP2-Pad10)") (class "Default")
      (node (ref "JP2") (pin "10") (pinfunction "10_10") (pintype "passive"))
      (node (ref "JP2") (pin "9") (pinfunction "9_9") (pintype "passive"))
    )
    (net (code "47") (name "Net-(JP5-Pad1)") (class "Default")
      (node (ref "JP5") (pin "1") (pinfunction "1_1") (pintype "passive"))
      (node (ref "Q2") (pin "B") (pinfunction "B_B") (pintype "passive"))
      (node (ref "R9") (pin "2") (pinfunction "2_2") (pintype "passive"))
    )
    (net (code "48") (name "Net-(L_1-C)") (class "Default")
      (node (ref "L_1") (pin "K") (pinfunction "C_K") (pintype "passive"))
      (node (ref "R1") (pin "2") (pinfunction "2_2") (pintype "passive"))
    )
    (net (code "49") (name "Net-(L_2-C)") (class "Default")
      (node (ref "L_2") (pin "K") (pinfunction "C_K") (pintype "passive"))
      (node (ref "R2") (pin "2") (pinfunction "2_2") (pintype "passive"))
    )
    (net (code "50") (name "Net-(L_3-C)") (class "Default")
      (node (ref "L_3") (pin "K") (pinfunction "C_K") (pintype "passive"))
      (node (ref "R3") (pin "2") (pinfunction "2_2") (pintype "passive"))
    )
    (net (code "51") (name "Net-(L_4-C)") (class "Default")
      (node (ref "L_4") (pin "K") (pinfunction "C_K") (pintype "passive"))
      (node (ref "R4") (pin "2") (pinfunction "2_2") (pintype "passive"))
    )
    (net (code "52") (name "Net-(L_5-C)") (class "Default")
      (node (ref "L_5") (pin "K") (pinfunction "C_K") (pintype "passive"))
      (node (ref "R5") (pin "2") (pinfunction "2_2") (pintype "passive"))
    )
    (net (code "53") (name "Net-(L_6-C)") (class "Default")
      (node (ref "L_6") (pin "K") (pinfunction "C_K") (pintype "passive"))
      (node (ref "R6") (pin "2") (pinfunction "2_2") (pintype "passive"))
    )
    (net (code "54") (name "Net-(L_7-C)") (class "Default")
      (node (ref "L_7") (pin "K") (pinfunction "C_K") (pintype "passive"))
      (node (ref "R7") (pin "2") (pinfunction "2_2") (pintype "passive"))
    )
    (net (code "55") (name "Net-(L_8-C)") (class "Default")
      (node (ref "L_8") (pin "K") (pinfunction "C_K") (pintype "passive"))
      (node (ref "R8") (pin "2") (pinfunction "2_2") (pintype "passive"))
    )
    (net (code "56") (name "Net-(L_9-C)") (class "Default")
      (node (ref "L_9") (pin "K") (pinfunction "C_K") (pintype "passive"))
      (node (ref "R_9") (pin "2") (pinfunction "2_2") (pintype "passive"))
    )
    (net (code "57") (name "Net-(L_10-C)") (class "Default")
      (node (ref "L_10") (pin "K") (pinfunction "C_K") (pintype "passive"))
      (node (ref "R_10") (pin "2") (pinfunction "2_2") (pintype "passive"))
    )
    (net (code "58") (name "Net-(L_11-C)") (class "Default")
      (node (ref "L_11") (pin "K") (pinfunction "C_K") (pintype "passive"))
      (node (ref "R_11") (pin "2") (pinfunction "2_2") (pintype "passive"))
    )
    (net (code "59") (name "Net-(L_12-C)") (class "Default")
      (node (ref "L_12") (pin "K") (pinfunction "C_K") (pintype "passive"))
      (node (ref "R_12") (pin "2") (pinfunction "2_2") (pintype "passive"))
    )
    (net (code "60") (name "Net-(L_13-C)") (class "Default")
      (node (ref "L_13") (pin "K") (pinfunction "C_K") (pintype "passive"))
      (node (ref "R_13") (pin "2") (pinfunction "2_2") (pintype "passive"))
    )
    (net (code "61") (name "Net-(L_14-C)") (class "Default")
      (node (ref "L_14") (pin "K") (pinfunction "C_K") (pintype "passive"))
      (node (ref "R_14") (pin "2") (pinfunction "2_2") (pintype "passive"))
    )
    (net (code "62") (name "Net-(L_15-C)") (class "Default")
      (node (ref "L_15") (pin "K") (pinfunction "C_K") (pintype "passive"))
      (node (ref "R15") (pin "2") (pinfunction "2_2") (pintype "passive"))
    )
    (net (code "63") (name "Net-(L_16-C)") (class "Default")
      (node (ref "L_16") (pin "K") (pinfunction "C_K") (pintype "passive"))
      (node (ref "R16") (pin "2") (pinfunction "2_2") (pintype "passive"))
    )
    (net (code "64") (name "Net-(L_17-C)") (class "Default")
      (node (ref "L_17") (pin "K") (pinfunction "C_K") (pintype "passive"))
      (node (ref "R17") (pin "2") (pinfunction "2_2") (pintype "passive"))
    )
    (net (code "65") (name "Net-(L_18-C)") (class "Default")
      (node (ref "L_18") (pin "K") (pinfunction "C_K") (pintype "passive"))
      (node (ref "R18") (pin "2") (pinfunction "2_2") (pintype "passive"))
    )
    (net (code "66") (name "Net-(L_19-C)") (class "Default")
      (node (ref "L_19") (pin "K") (pinfunction "C_K") (pintype "passive"))
      (node (ref "R19") (pin "2") (pinfunction "2_2") (pintype "passive"))
    )
    (net (code "67") (name "Net-(L_20-C)") (class "Default")
      (node (ref "L_20") (pin "K") (pinfunction "C_K") (pintype "passive"))
      (node (ref "R20") (pin "2") (pinfunction "2_2") (pintype "passive"))
    )
    (net (code "68") (name "Net-(L_21-C)") (class "Default")
      (node (ref "L_21") (pin "K") (pinfunction "C_K") (pintype "passive"))
      (node (ref "R21") (pin "2") (pinfunction "2_2") (pintype "passive"))
    )
    (net (code "69") (name "Net-(L_22-C)") (class "Default")
      (node (ref "L_22") (pin "K") (pinfunction "C_K") (pintype "passive"))
      (node (ref "R22") (pin "2") (pinfunction "2_2") (pintype "passive"))
    )
    (net (code "70") (name "Net-(L_23-C)") (class "Default")
      (node (ref "L_23") (pin "K") (pinfunction "C_K") (pintype "passive"))
      (node (ref "R23") (pin "2") (pinfunction "2_2") (pintype "passive"))
    )
    (net (code "71") (name "Net-(L_24-C)") (class "Default")
      (node (ref "L_24") (pin "K") (pinfunction "C_K") (pintype "passive"))
      (node (ref "R24") (pin "2") (pinfunction "2_2") (pintype "passive"))
    )
    (net (code "72") (name "Net-(L_25-C)") (class "Default")
      (node (ref "L_25") (pin "K") (pinfunction "C_K") (pintype "passive"))
      (node (ref "R25") (pin "2") (pinfunction "2_2") (pintype "passive"))
    )
    (net (code "73") (name "Net-(L_26-C)") (class "Default")
      (node (ref "L_26") (pin "K") (pinfunction "C_K") (pintype "passive"))
      (node (ref "R26") (pin "2") (pinfunction "2_2") (pintype "passive"))
    )
    (net (code "74") (name "Net-(L_27-C)") (class "Default")
      (node (ref "L_27") (pin "K") (pinfunction "C_K") (pintype "passive"))
      (node (ref "R27") (pin "2") (pinfunction "2_2") (pintype "passive"))
    )
    (net (code "75") (name "Net-(L_28-C)") (class "Default")
      (node (ref "L_28") (pin "K") (pinfunction "C_K") (pintype "passive"))
      (node (ref "R28") (pin "2") (pinfunction "2_2") (pintype "passive"))
    )
    (net (code "76") (name "Net-(L_29-C)") (class "Default")
      (node (ref "L_29") (pin "K") (pinfunction "C_K") (pintype "passive"))
      (node (ref "R29") (pin "2") (pinfunction "2_2") (pintype "passive"))
    )
    (net (code "77") (name "Net-(L_30-C)") (class "Default")
      (node (ref "L_30") (pin "K") (pinfunction "C_K") (pintype "passive"))
      (node (ref "R30") (pin "2") (pinfunction "2_2") (pintype "passive"))
    )
    (net (code "78") (name "Net-(_D1-C)") (class "Default")
      (node (ref "B1") (pin "B1") (pinfunction "2_B1") (pintype "passive"))
      (node (ref "B1") (pin "B2") (pinfunction "2_B2") (pintype "passive"))
      (node (ref "_D1") (pin "K") (pinfunction "C_K") (pintype "passive"))
    )
    (net (code "79") (name "Net-(_D2-C)") (class "Default")
      (node (ref "B2") (pin "B1") (pinfunction "2_B1") (pintype "passive"))
      (node (ref "B2") (pin "B2") (pinfunction "2_B2") (pintype "passive"))
      (node (ref "_D2") (pin "K") (pinfunction "C_K") (pintype "passive"))
    )
    (net (code "80") (name "Net-(_D3-C)") (class "Default")
      (node (ref "B3") (pin "B1") (pinfunction "2_B1") (pintype "passive"))
      (node (ref "B3") (pin "B2") (pinfunction "2_B2") (pintype "passive"))
      (node (ref "_D3") (pin "K") (pinfunction "C_K") (pintype "passive"))
    )
    (net (code "81") (name "Net-(_D4-C)") (class "Default")
      (node (ref "B4") (pin "B1") (pinfunction "2_B1") (pintype "passive"))
      (node (ref "B4") (pin "B2") (pinfunction "2_B2") (pintype "passive"))
      (node (ref "_D4") (pin "K") (pinfunction "C_K") (pintype "passive"))
    )
    (net (code "82") (name "Net-(_D5-C)") (class "Default")
      (node (ref "B5") (pin "B1") (pinfunction "2_B1") (pintype "passive"))
      (node (ref "B5") (pin "B2") (pinfunction "2_B2") (pintype "passive"))
      (node (ref "_D5") (pin "K") (pinfunction "C_K") (pintype "passive"))
    )
    (net (code "83") (name "Net-(_D6-C)") (class "Default")
      (node (ref "B6") (pin "B1") (pinfunction "2_B1") (pintype "passive"))
      (node (ref "B6") (pin "B2") (pinfunction "2_B2") (pintype "passive"))
      (node (ref "_D6") (pin "K") (pinfunction "C_K") (pintype "passive"))
    )
    (net (code "84") (name "Net-(_D7-C)") (class "Default")
      (node (ref "B7") (pin "B1") (pinfunction "2_B1") (pintype "passive"))
      (node (ref "B7") (pin "B2") (pinfunction "2_B2") (pintype "passive"))
      (node (ref "_D7") (pin "K") (pinfunction "C_K") (pintype "passive"))
    )
    (net (code "85") (name "Net-(_D8-C)") (class "Default")
      (node (ref "B8") (pin "B1") (pinfunction "2_B1") (pintype "passive"))
      (node (ref "B8") (pin "B2") (pinfunction "2_B2") (pintype "passive"))
      (node (ref "_D8") (pin "K") (pinfunction "C_K") (pintype "passive"))
    )
    (net (code "86") (name "Net-(_D9-C)") (class "Default")
      (node (ref "B9") (pin "B1") (pinfunction "2_B1") (pintype "passive"))
      (node (ref "B9") (pin "B2") (pinfunction "2_B2") (pintype "passive"))
      (node (ref "_D9") (pin "K") (pinfunction "C_K") (pintype "passive"))
    )
    (net (code "87") (name "Net-(_D10-C)") (class "Default")
      (node (ref "B10") (pin "B1") (pinfunction "2_B1") (pintype "passive"))
      (node (ref "B10") (pin "B2") (pinfunction "2_B2") (pintype "passive"))
      (node (ref "_D10") (pin "K") (pinfunction "C_K") (pintype "passive"))
    )
    (net (code "88") (name "Net-(_D11-C)") (class "Default")
      (node (ref "B11") (pin "B1") (pinfunction "2_B1") (pintype "passive"))
      (node (ref "B11") (pin "B2") (pinfunction "2_B2") (pintype "passive"))
      (node (ref "_D11") (pin "K") (pinfunction "C_K") (pintype "passive"))
    )
    (net (code "89") (name "Net-(_D12-C)") (class "Default")
      (node (ref "B12") (pin "B1") (pinfunction "2_B1") (pintype "passive"))
      (node (ref "B12") (pin "B2") (pinfunction "2_B2") (pintype "passive"))
      (node (ref "_D12") (pin "K") (pinfunction "C_K") (pintype "passive"))
    )
    (net (code "90") (name "Net-(_D13-C)") (class "Default")
      (node (ref "B13") (pin "B1") (pinfunction "2_B1") (pintype "passive"))
      (node (ref "B13") (pin "B2") (pinfunction "2_B2") (pintype "passive"))
      (node (ref "_D13") (pin "K") (pinfunction "C_K") (pintype "passive"))
    )
    (net (code "91") (name "Net-(_D14-C)") (class "Default")
      (node (ref "B14") (pin "B1") (pinfunction "2_B1") (pintype "passive"))
      (node (ref "B14") (pin "B2") (pinfunction "2_B2") (pintype "passive"))
      (node (ref "_D14") (pin "K") (pinfunction "C_K") (pintype "passive"))
    )
    (net (code "92") (name "Net-(_D15-C)") (class "Default")
      (node (ref "B15") (pin "B1") (pinfunction "2_B1") (pintype "passive"))
      (node (ref "B15") (pin "B2") (pinfunction "2_B2") (pintype "passive"))
      (node (ref "_D15") (pin "K") (pinfunction "C_K") (pintype "passive"))
    )
    (net (code "93") (name "Net-(_D16-C)") (class "Default")
      (node (ref "B16") (pin "B1") (pinfunction "2_B1") (pintype "passive"))
      (node (ref "B16") (pin "B2") (pinfunction "2_B2") (pintype "passive"))
      (node (ref "_D16") (pin "K") (pinfunction "C_K") (pintype "passive"))
    )
    (net (code "94") (name "Net-(_D17-C)") (class "Default")
      (node (ref "B17") (pin "B1") (pinfunction "2_B1") (pintype "passive"))
      (node (ref "B17") (pin "B2") (pinfunction "2_B2") (pintype "passive"))
      (node (ref "_D17") (pin "K") (pinfunction "C_K") (pintype "passive"))
    )
    (net (code "95") (name "Net-(_D18-C)") (class "Default")
      (node (ref "B18") (pin "B1") (pinfunction "2_B1") (pintype "passive"))
      (node (ref "B18") (pin "B2") (pinfunction "2_B2") (pintype "passive"))
      (node (ref "_D18") (pin "K") (pinfunction "C_K") (pintype "passive"))
    )
    (net (code "96") (name "Net-(_D19-C)") (class "Default")
      (node (ref "B19") (pin "B1") (pinfunction "2_B1") (pintype "passive"))
      (node (ref "B19") (pin "B2") (pinfunction "2_B2") (pintype "passive"))
      (node (ref "_D19") (pin "K") (pinfunction "C_K") (pintype "passive"))
    )
    (net (code "97") (name "Net-(_D20-C)") (class "Default")
      (node (ref "B20") (pin "B1") (pinfunction "2_B1") (pintype "passive"))
      (node (ref "B20") (pin "B2") (pinfunction "2_B2") (pintype "passive"))
      (node (ref "_D20") (pin "K") (pinfunction "C_K") (pintype "passive"))
    )
    (net (code "98") (name "Net-(_D21-C)") (class "Default")
      (node (ref "B21") (pin "B1") (pinfunction "2_B1") (pintype "passive"))
      (node (ref "B21") (pin "B2") (pinfunction "2_B2") (pintype "passive"))
      (node (ref "_D21") (pin "K") (pinfunction "C_K") (pintype "passive"))
    )
    (net (code "99") (name "Net-(_D22-C)") (class "Default")
      (node (ref "B22") (pin "B1") (pinfunction "2_B1") (pintype "passive"))
      (node (ref "B22") (pin "B2") (pinfunction "2_B2") (pintype "passive"))
      (node (ref "_D22") (pin "K") (pinfunction "C_K") (pintype "passive"))
    )
    (net (code "100") (name "Net-(_D23-C)") (class "Default")
      (node (ref "B23") (pin "B1") (pinfunction "2_B1") (pintype "passive"))
      (node (ref "B23") (pin "B2") (pinfunction "2_B2") (pintype "passive"))
      (node (ref "_D23") (pin "K") (pinfunction "C_K") (pintype "passive"))
    )
    (net (code "101") (name "Net-(_D24-C)") (class "Default")
      (node (ref "B24") (pin "B1") (pinfunction "2_B1") (pintype "passive"))
      (node (ref "B24") (pin "B2") (pinfunction "2_B2") (pintype "passive"))
      (node (ref "_D24") (pin "K") (pinfunction "C_K") (pintype "passive"))
    )
    (net (code "102") (name "Net-(_D25-C)") (class "Default")
      (node (ref "B25") (pin "B1") (pinfunction "2_B1") (pintype "passive"))
      (node (ref "B25") (pin "B2") (pinfunction "2_B2") (pintype "passive"))
      (node (ref "_D25") (pin "K") (pinfunction "C_K") (pintype "passive"))
    )
    (net (code "103") (name "Net-(_D26-C)") (class "Default")
      (node (ref "B26") (pin "B1") (pinfunction "2_B1") (pintype "passive"))
      (node (ref "B26") (pin "B2") (pinfunction "2_B2") (pintype "passive"))
      (node (ref "_D26") (pin "K") (pinfunction "C_K") (pintype "passive"))
    )
    (net (code "104") (name "Net-(_D27-C)") (class "Default")
      (node (ref "B27") (pin "B1") (pinfunction "2_B1") (pintype "passive"))
      (node (ref "B27") (pin "B2") (pinfunction "2_B2") (pintype "passive"))
      (node (ref "_D27") (pin "K") (pinfunction "C_K") (pintype "passive"))
    )
    (net (code "105") (name "Net-(_D28-C)") (class "Default")
      (node (ref "B28") (pin "B1") (pinfunction "2_B1") (pintype "passive"))
      (node (ref "B28") (pin "B2") (pinfunction "2_B2") (pintype "passive"))
      (node (ref "_D28") (pin "K") (pinfunction "C_K") (pintype "passive"))
    )
    (net (code "106") (name "Net-(_D29-C)") (class "Default")
      (node (ref "B29") (pin "B1") (pinfunction "2_B1") (pintype "passive"))
      (node (ref "B29") (pin "B2") (pinfunction "2_B2") (pintype "passive"))
      (node (ref "_D29") (pin "K") (pinfunction "C_K") (pintype "passive"))
    )
    (net (code "107") (name "Net-(_D30-C)") (class "Default")
      (node (ref "B30") (pin "B1") (pinfunction "2_B1") (pintype "passive"))
      (node (ref "B30") (pin "B2") (pinfunction "2_B2") (pintype "passive"))
      (node (ref "_D30") (pin "K") (pinfunction "C_K") (pintype "passive"))
    )
    (net (code "108") (name "Net-(_D31-C)") (class "Default")
      (node (ref "B_31") (pin "B1") (pinfunction "2_B1") (pintype "passive"))
      (node (ref "B_31") (pin "B2") (pinfunction "2_B2") (pintype "passive"))
      (node (ref "_D31") (pin "K") (pinfunction "C_K") (pintype "passive"))
    )
    (net (code "109") (name "Net-(_D32-C)") (class "Default")
      (node (ref "B32") (pin "B1") (pinfunction "2_B1") (pintype "passive"))
      (node (ref "B32") (pin "B2") (pinfunction "2_B2") (pintype "passive"))
      (node (ref "_D32") (pin "K") (pinfunction "C_K") (pintype "passive"))
    )
    (net (code "110") (name "Net-(_L_31-C)") (class "Default")
      (node (ref "R_31") (pin "2") (pinfunction "2_2") (pintype "passive"))
      (node (ref "_L_31") (pin "K") (pinfunction "C_K") (pintype "passive"))
    )
    (net (code "111") (name "Net-(_L_32-C)") (class "Default")
      (node (ref "_L_32") (pin "K") (pinfunction "C_K") (pintype "passive"))
      (node (ref "_R_32") (pin "2") (pinfunction "2_2") (pintype "passive"))
    )
    (net (code "112") (name "unconnected-(IC2A-QG-Pad6)") (class "Default")
      (node (ref "IC2") (pin "6") (pinfunction "QG_6") (pintype "tri_state"))
    )
    (net (code "113") (name "unconnected-(IC2A-QH-Pad7)") (class "Default")
      (node (ref "IC2") (pin "7") (pinfunction "QH_7") (pintype "tri_state"))
    )
    (net (code "114") (name "unconnected-(IC3A-QH*-Pad9)") (class "Default")
      (node (ref "IC3") (pin "9") (pinfunction "QH*_9") (pintype "tri_state"))
    )
    (net (code "115") (name "unconnected-(IC4D-I-Pad9)") (class "Default")
      (node (ref "IC4") (pin "9") (pinfunction "I_9") (pintype "input"))
    )
    (net (code "116") (name "unconnected-(IC4D-O-Pad10)") (class "Default")
      (node (ref "IC4") (pin "10") (pinfunction "O_10") (pintype "output"))
    )
    (net (code "117") (name "unconnected-(IC4E-I-Pad11)") (class "Default")
      (node (ref "IC4") (pin "11") (pinfunction "I_11") (pintype "input"))
    )
    (net (code "118") (name "unconnected-(IC4E-O-Pad12)") (class "Default")
      (node (ref "IC4") (pin "12") (pinfunction "O_12") (pintype "output"))
    )
    (net (code "119") (name "unconnected-(IC4F-I-Pad14)") (class "Default")
      (node (ref "IC4") (pin "14") (pinfunction "I_14") (pintype "input"))
    )
    (net (code "120") (name "unconnected-(IC4F-O-Pad15)") (class "Default")
      (node (ref "IC4") (pin "15") (pinfunction "O_15") (pintype "output"))
    )
    (net (code "121") (name "unconnected-(IC_1-ADC6-Pad19)") (class "Default")
      (node (ref "IC_1") (pin "19") (pinfunction "ADC6_19") (pintype "input"))
    )
    (net (code "122") (name "unconnected-(IC_1-ADC7-Pad22)") (class "Default")
      (node (ref "IC_1") (pin "22") (pinfunction "ADC7_22") (pintype "input"))
    )
    (net (code "123") (name "unconnected-(IC_1-PC1-Pad24)") (class "Default")
      (node (ref "IC_1") (pin "24") (pinfunction "PC1_24") (pintype "bidirectional"))
    )
    (net (code "124") (name "unconnected-(IC_1-PC2-Pad25)") (class "Default")
      (node (ref "IC_1") (pin "25") (pinfunction "PC2_25") (pintype "bidirectional"))
    )
    (net (code "125") (name "unconnected-(U$8-CARD_DETECTION-PadCD)") (class "Default")
      (node (ref "U$8") (pin "CD") (pinfunction "CARD_DETECTION_CD") (pintype "bidirectional"))
    )
    (net (code "126") (name "unconnected-(U$8-DAT1-Pad8)") (class "Default")
      (node (ref "U$8") (pin "8") (pinfunction "DAT1_8") (pintype "bidirectional"))
    )
    (net (code "127") (name "unconnected-(U$8-DAT2-Pad1)") (class "Default")
      (node (ref "U$8") (pin "1") (pinfunction "DAT2_1") (pintype "bidirectional"))
    )
    (net (code "128") (name "unconnected-(U3-BP-Pad4)") (class "Default")
      (node (ref "U3") (pin "4") (pinfunction "BP_4") (pintype "input"))
    )
  )
)
